# sensor_board.net
KiCad netlist of a schematic drawn in EAGLE
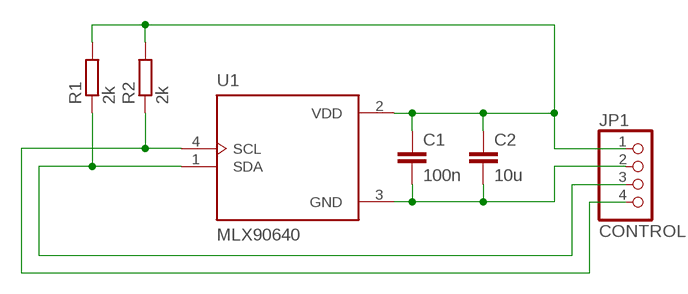
[diagram p0: schematic, sheet 1]

(export (version "E")
  (design (tool "Eeschema 10.0.6"))
  (components
    (comp (ref "C1")
      (value "100n")
      (footprint "eagle-import:C0805")
      (libsource (lib "eagle-import") (part "C-EUC0805"))
    )
    (comp (ref "C2")
      (value "10u")
      (footprint "eagle-import:C0805")
      (libsource (lib "eagle-import") (part "C-EUC0805"))
    )
    (comp (ref "JP1")
      (value "CONTROL")
      (footprint "eagle-import:1X04")
      (libsource (lib "eagle-import") (part "PINHD-1X4"))
    )
    (comp (ref "R1")
      (value "2k")
      (footprint "eagle-import:R0805")
      (libsource (lib "eagle-import") (part "R-EU_R0805"))
    )
    (comp (ref "R2")
      (value "2k")
      (footprint "eagle-import:R0805")
      (libsource (lib "eagle-import") (part "R-EU_R0805"))
    )
    (comp (ref "U1")
      (value "MLX90640")
      (footprint "eagle-import:TO292P945H1165-4")
      (fields (field (name "MF") "Melexis Technologies NV") (field (name "MP") "MLX90640ESF-BAB-000-TU"))
      (libsource (lib "eagle-import") (part "MLX90640ESF-BAB-000-TU"))
    )
  )
  (nets
    (net (code "1") (name "Net-(U1-GND)") (class "Default")
      (node (ref "C1") (pin "2") (pinfunction "2_2") (pintype "passive"))
      (node (ref "C2") (pin "2") (pinfunction "2_2") (pintype "passive"))
      (node (ref "JP1") (pin "2") (pinfunction "2_2") (pintype "passive"))
      (node (ref "U1") (pin "3") (pinfunction "GND_3") (pintype "power_in"))
    )
    (net (code "2") (name "Net-(U1-SCL)") (class "Default")
      (node (ref "JP1") (pin "4") (pinfunction "4_4") (pintype "passive"))
      (node (ref "R2") (pin "1") (pinfunction "1_1") (pintype "passive"))
      (node (ref "U1") (pin "4") (pinfunction "SCL_4") (pintype "input"))
    )
    (net (code "3") (name "Net-(U1-SDA)") (class "Default")
      (node (ref "JP1") (pin "3") (pinfunction "3_3") (pintype "passive"))
      (node (ref "R1") (pin "1") (pinfunction "1_1") (pintype "passive"))
      (node (ref "U1") (pin "1") (pinfunction "SDA_1") (pintype "bidirectional"))
    )
    (net (code "4") (name "Net-(U1-VDD)") (class "Default")
      (node (ref "C1") (pin "1") (pinfunction "1_1") (pintype "passive"))
      (node (ref "C2") (pin "1") (pinfunction "1_1") (pintype "passive"))
      (node (ref "JP1") (pin "1") (pinfunction "1_1") (pintype "passive"))
      (node (ref "R1") (pin "2") (pinfunction "2_2") (pintype "passive"))
      (node (ref "R2") (pin "2") (pinfunction "2_2") (pintype "passive"))
      (node (ref "U1") (pin "2") (pinfunction "VDD_2") (pintype "power_in"))
    )
  )
)
